# AC_Measure.net
KiCad netlist of a schematic drawn in Altium Designer
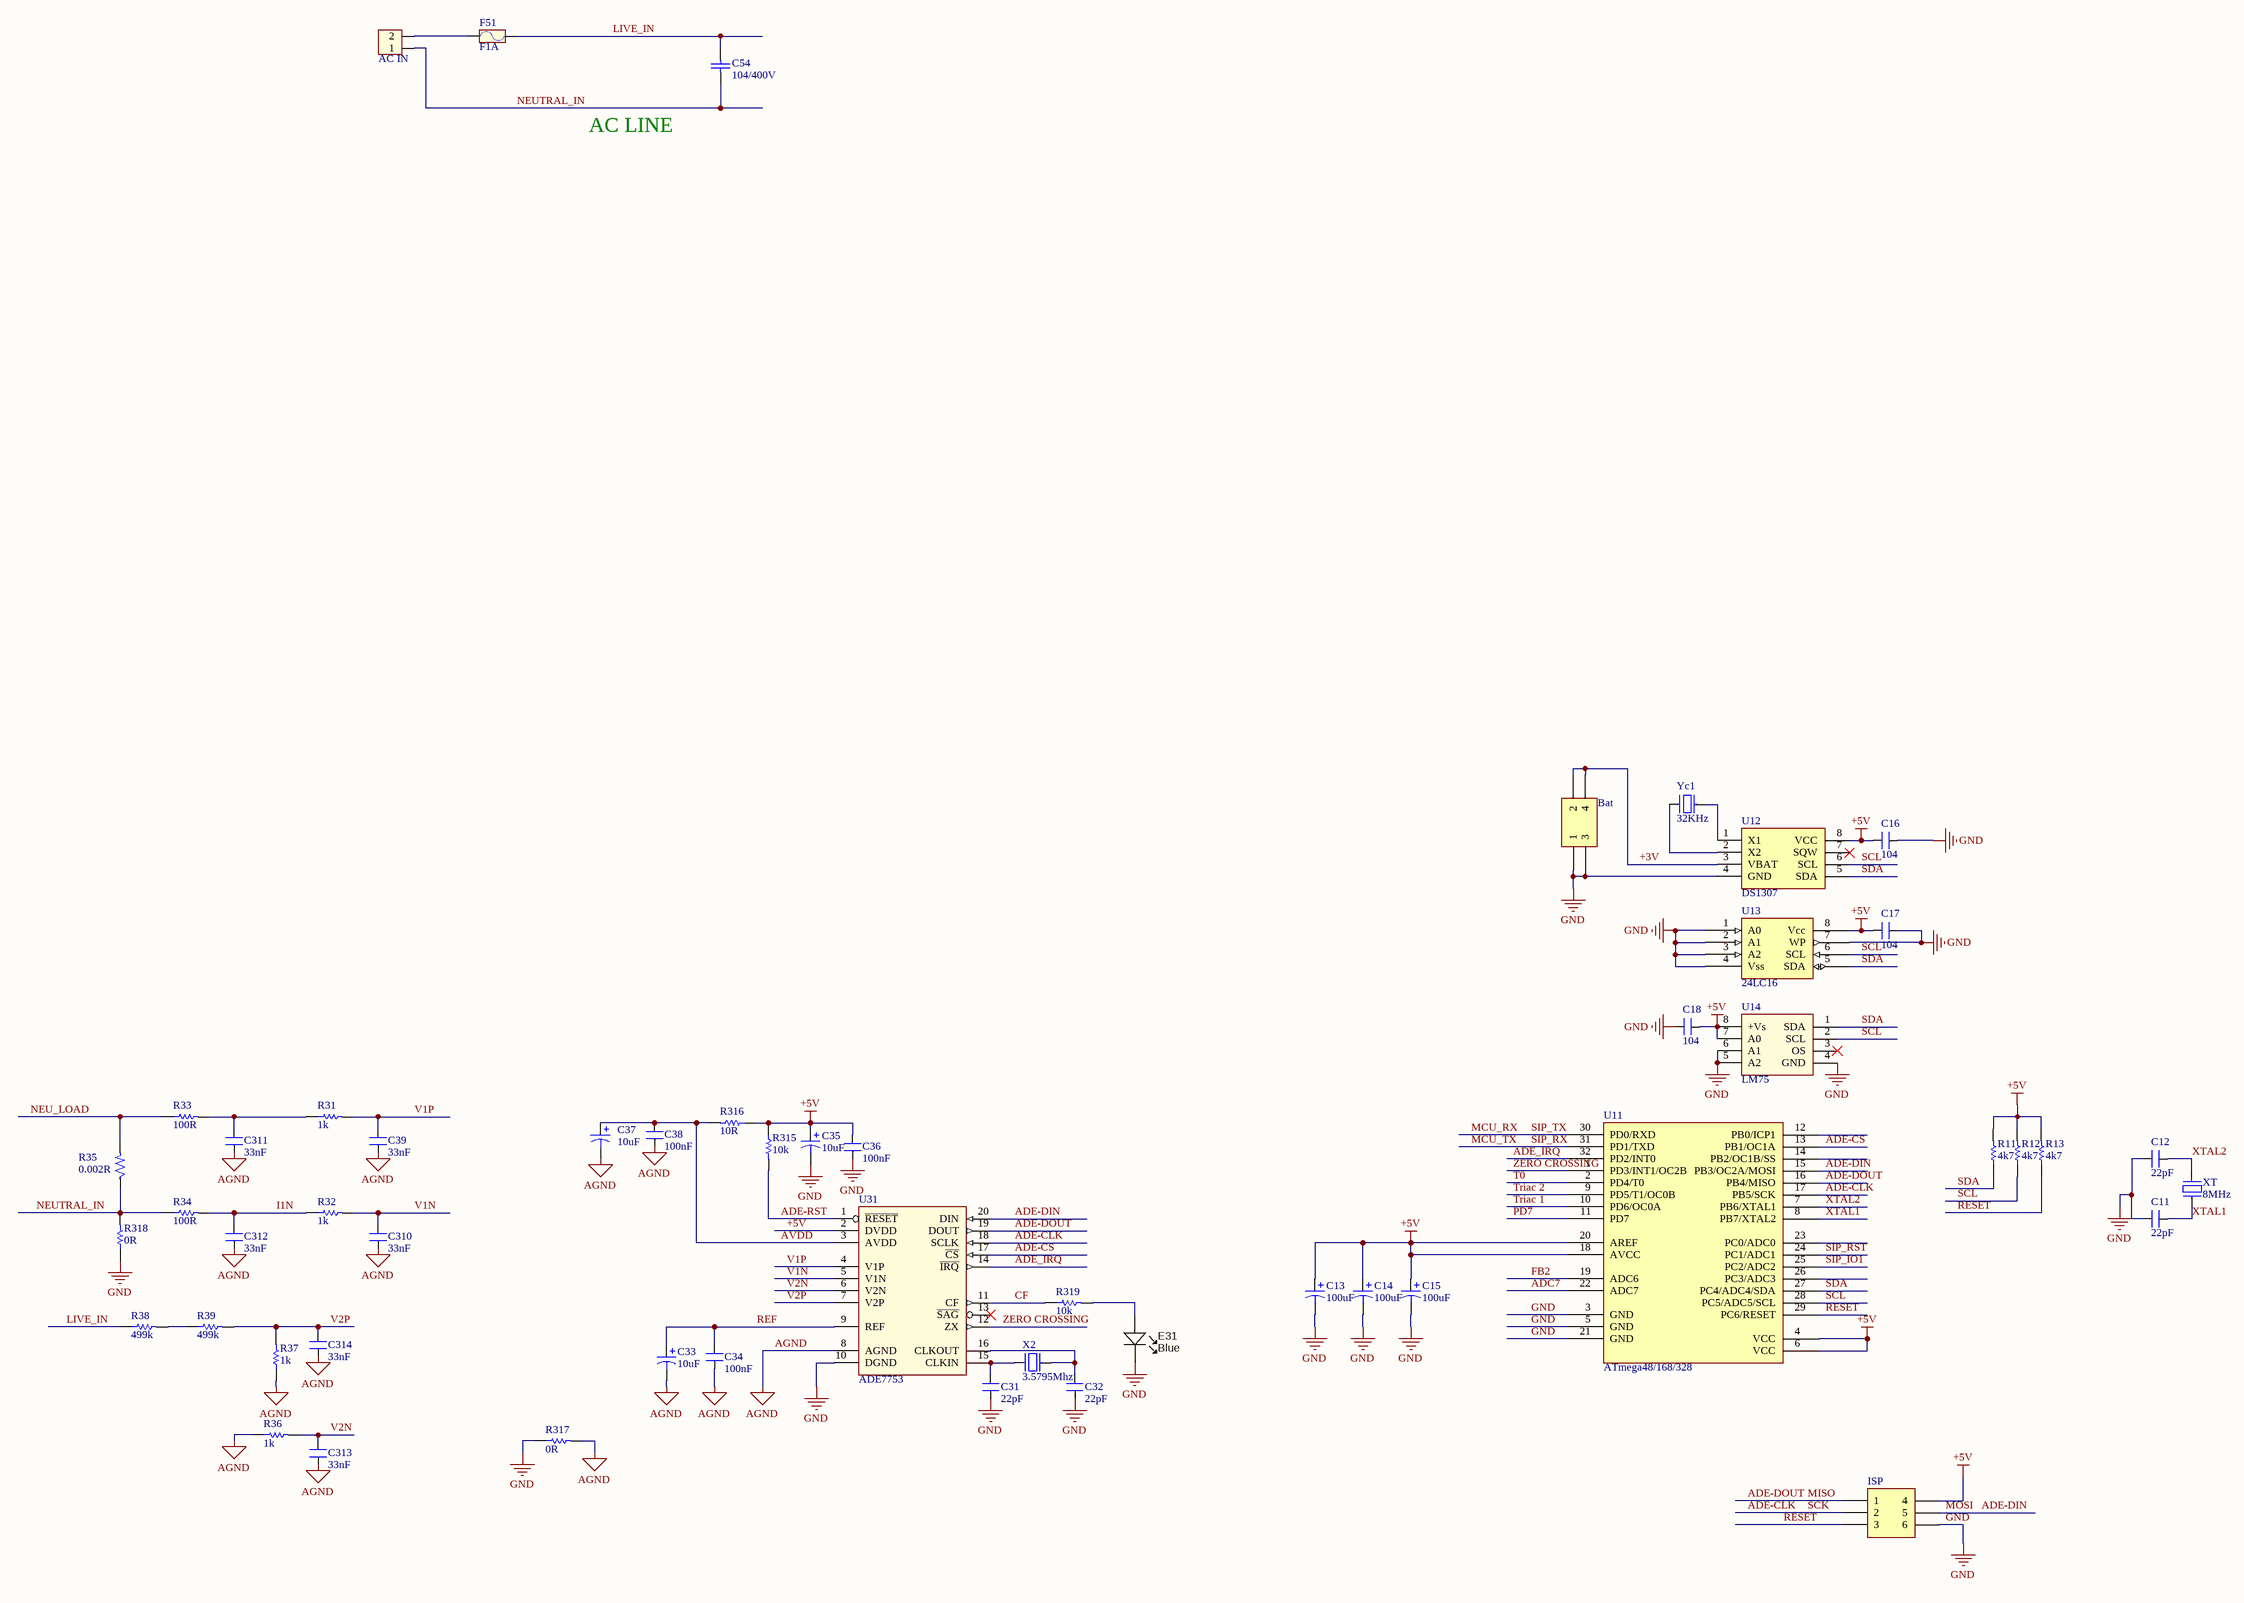
[diagram p0: AC_Measure.SchDoc]

(export (version "E")
  (design (tool "Eeschema 10.0.6"))
  (components
    (comp (ref "AC IN")
      (value "JP2")
      (footprint "CON2")
      (description "Connector 2")
      (libsource (lib "syhaunguyen") (part "Con2"))
    )
    (comp (ref "Bat")
      (value "Header 2X2")
      (footprint "HDR2X2")
      (description "Header, 2-Pin, Dual row")
      (fields (field (name "PUBLISHER") "Altium Limited"))
      (libsource (lib "Miscellaneous Connectors") (part "Header 2X2"))
    )
    (comp (ref "C11")
      (value "22pF")
      (footprint "CAPC1608N")
      (fields (field (name "Comment") "CAP NP"))
      (libsource (lib "Tuan") (part "CAP NP"))
    )
    (comp (ref "C12")
      (value "22pF")
      (footprint "CAPC1608N")
      (fields (field (name "Comment") "CAP NP"))
      (libsource (lib "Tuan") (part "CAP NP"))
    )
    (comp (ref "C13")
      (value "100uF")
      (footprint "CAPC2012N_F")
      (fields (field (name "Comment") "Cap"))
      (libsource (lib "Tuan") (part "Cap"))
    )
    (comp (ref "C14")
      (value "100uF")
      (footprint "CAPC2012N_F")
      (fields (field (name "Comment") "Cap"))
      (libsource (lib "Tuan") (part "Cap"))
    )
    (comp (ref "C15")
      (value "100uF")
      (footprint "CAPC2012N_F")
      (fields (field (name "Comment") "Cap"))
      (libsource (lib "Tuan") (part "Cap"))
    )
    (comp (ref "C16")
      (value "104")
      (footprint "CAPC2012N_F")
      (fields (field (name "Comment") "CAP NP"))
      (libsource (lib "Tuan") (part "CAP NP"))
    )
    (comp (ref "C17")
      (value "104")
      (footprint "CAPC2012N_F")
      (fields (field (name "Comment") "CAP NP"))
      (libsource (lib "Tuan") (part "CAP NP"))
    )
    (comp (ref "C18")
      (value "104")
      (footprint "CAPC2012N_F")
      (fields (field (name "Comment") "CAP NP"))
      (libsource (lib "Tuan") (part "CAP NP"))
    )
    (comp (ref "C31")
      (value "22pF")
      (footprint "CAPC1608N")
      (fields (field (name "Comment") "CAP NP"))
      (libsource (lib "ELS-PLC-2.0") (part "CAP NP"))
    )
    (comp (ref "C32")
      (value "22pF")
      (footprint "CAPC1608N")
      (fields (field (name "Comment") "CAP NP"))
      (libsource (lib "ELS-PLC-2.0") (part "CAP NP"))
    )
    (comp (ref "C33")
      (value "10uF")
      (footprint "CAPC2012N_F")
      (fields (field (name "Comment") "Cap"))
      (libsource (lib "Tuan") (part "Cap"))
    )
    (comp (ref "C34")
      (value "100nF")
      (footprint "CAPC1608N")
      (fields (field (name "Comment") "CAP NP"))
      (libsource (lib "ELS-PLC-2.0") (part "CAP NP"))
    )
    (comp (ref "C35")
      (value "10uF")
      (footprint "CAPC2012N_F")
      (fields (field (name "Comment") "Cap"))
      (libsource (lib "Tuan") (part "Cap"))
    )
    (comp (ref "C36")
      (value "100nF")
      (footprint "CAPC1608N")
      (fields (field (name "Comment") "CAP NP"))
      (libsource (lib "ELS-PLC-2.0") (part "CAP NP"))
    )
    (comp (ref "C37")
      (value "10uF")
      (footprint "CAPC2012N_F")
      (fields (field (name "Comment") "Cap"))
      (libsource (lib "Tuan") (part "Cap"))
    )
    (comp (ref "C38")
      (value "100nF")
      (footprint "CAPC1608N")
      (fields (field (name "Comment") "CAP NP"))
      (libsource (lib "ELS-PLC-2.0") (part "CAP NP"))
    )
    (comp (ref "C39")
      (value "33nF")
      (footprint "CAPC1608N")
      (fields (field (name "Comment") "CAP NP"))
      (libsource (lib "ELS-PLC-2.0") (part "CAP NP"))
    )
    (comp (ref "C54")
      (value "104/400V")
      (footprint "CN3")
      (description "Capacitor")
      (fields (field (name "PUBLISHER") "Altium Limited"))
      (libsource (lib "Miscellaneous Devices") (part "Cap"))
    )
    (comp (ref "C310")
      (value "33nF")
      (footprint "CAPC1608N")
      (fields (field (name "Comment") "CAP NP"))
      (libsource (lib "ELS-PLC-2.0") (part "CAP NP"))
    )
    (comp (ref "C311")
      (value "33nF")
      (footprint "CAPC1608N")
      (fields (field (name "Comment") "CAP NP"))
      (libsource (lib "ELS-PLC-2.0") (part "CAP NP"))
    )
    (comp (ref "C312")
      (value "33nF")
      (footprint "CAPC1608N")
      (fields (field (name "Comment") "CAP NP"))
      (libsource (lib "ELS-PLC-2.0") (part "CAP NP"))
    )
    (comp (ref "C313")
      (value "33nF")
      (footprint "CAPC1608N")
      (fields (field (name "Comment") "CAP NP"))
      (libsource (lib "ELS-PLC-2.0") (part "CAP NP"))
    )
    (comp (ref "C314")
      (value "33nF")
      (footprint "CAPC1608N")
      (fields (field (name "Comment") "CAP NP"))
      (libsource (lib "ELS-PLC-2.0") (part "CAP NP"))
    )
    (comp (ref "E31")
      (value "Blue")
      (footprint "LED-0805-K")
      (description "LED 0805 SMD Blue 100mcd 470nm")
      (fields (field (name "COLOR") "Blue"))
      (libsource (lib "PBL - Light Sources") (part "LED_SMD_Blue_0805_100mcd"))
    )
    (comp (ref "F51")
      (value "F1A")
      (footprint "FUSE2")
      (description "Fuse")
      (fields (field (name "DESIGNED BY") "VanDungEvn"))
      (libsource (lib "syhaunguyen") (part "Fuse"))
    )
    (comp (ref "ISP")
      (value "Header 3X2A")
      (footprint "HDR2X3_CEN")
      (description "Header, 3-Pin, Dual row")
      (fields (field (name "PUBLISHER") "Altium Limited"))
      (libsource (lib "Miscellaneous Connectors") (part "Header 3X2A"))
    )
    (comp (ref "R11")
      (value "4k7")
      (footprint "RESC1608N_ZERO")
      (fields (field (name "Comment") "Res"))
      (libsource (lib "Tuan") (part "Res"))
    )
    (comp (ref "R12")
      (value "4k7")
      (footprint "RESC1608N_ZERO")
      (fields (field (name "Comment") "Res"))
      (libsource (lib "Tuan") (part "Res"))
    )
    (comp (ref "R13")
      (value "4k7")
      (footprint "RESC1608N_ZERO")
      (fields (field (name "Comment") "Res"))
      (libsource (lib "Tuan") (part "Res"))
    )
    (comp (ref "R31")
      (value "1k")
      (footprint "RESC1608N_ZERO")
      (fields (field (name "Comment") "Res"))
      (libsource (lib "Tuan") (part "Res"))
    )
    (comp (ref "R32")
      (value "1k")
      (footprint "RESC1608N_ZERO")
      (fields (field (name "Comment") "Res"))
      (libsource (lib "Tuan") (part "Res"))
    )
    (comp (ref "R33")
      (value "100R")
      (footprint "RESC1608N_ZERO")
      (fields (field (name "Comment") "Res"))
      (libsource (lib "Tuan") (part "Res"))
    )
    (comp (ref "R34")
      (value "100R")
      (footprint "RESC1608N_ZERO")
      (fields (field (name "Comment") "Res"))
      (libsource (lib "Tuan") (part "Res"))
    )
    (comp (ref "R35")
      (value "0.002R")
      (footprint "RESC6332N")
      (description "Resistor 1/4W")
      (libsource (lib "syhaunguyen") (part "R"))
    )
    (comp (ref "R36")
      (value "1k")
      (footprint "RESC1608N_ZERO")
      (fields (field (name "Comment") "Res"))
      (libsource (lib "Tuan") (part "Res"))
    )
    (comp (ref "R37")
      (value "1k")
      (footprint "RESC1608N_ZERO")
      (fields (field (name "Comment") "Res"))
      (libsource (lib "Tuan") (part "Res"))
    )
    (comp (ref "R38")
      (value "499k")
      (footprint "RESC2012N_F")
      (fields (field (name "Comment") "Res"))
      (libsource (lib "Tuan") (part "Res"))
    )
    (comp (ref "R39")
      (value "499k")
      (footprint "RESC2012N_F")
      (fields (field (name "Comment") "Res"))
      (libsource (lib "Tuan") (part "Res"))
    )
    (comp (ref "R315")
      (value "10k")
      (footprint "RESC1608N_ZERO")
      (fields (field (name "Comment") "Res"))
      (libsource (lib "Tuan") (part "Res"))
    )
    (comp (ref "R316")
      (value "10R")
      (footprint "RESC2012N_F")
      (fields (field (name "Comment") "Res"))
      (libsource (lib "Tuan") (part "Res"))
    )
    (comp (ref "R317")
      (value "0R")
      (footprint "RESC2012N_F")
      (fields (field (name "Comment") "Res"))
      (libsource (lib "Tuan") (part "Res"))
    )
    (comp (ref "R318")
      (value "0R")
      (footprint "RESC2012N_F")
      (fields (field (name "Comment") "Res"))
      (libsource (lib "Tuan") (part "Res"))
    )
    (comp (ref "R319")
      (value "10k")
      (footprint "RESC1608N_ZERO")
      (fields (field (name "Comment") "Res"))
      (libsource (lib "Tuan") (part "Res"))
    )
    (comp (ref "U11")
      (value "ATmega48/168/328")
      (footprint "32A_N")
      (libsource (lib "Tuan") (part "ATmega48/168/328"))
    )
    (comp (ref "U12")
      (value "DS1307")
      (footprint "SOIC-8")
      (description "Real Timer Serial")
      (libsource (lib "MLab Miscellaneous Devices") (part "DS1307"))
    )
    (comp (ref "U13")
      (value "24LC16")
      (footprint "SOIC-8")
      (libsource (lib "PhamTu_IntLib") (part "24LC04B"))
    )
    (comp (ref "U14") (value "LM75") (footprint "SOIC-8") (libsource (lib "heromap") (part "LM75")))
    (comp (ref "U31")
      (value "ADE7753")
      (footprint "TSSOP-20")
      (description "Single-Phase Multifunction Metering IC with di/dt Sensor Interface")
      (libsource (lib "heromap") (part "ADE7753"))
    )
    (comp (ref "X2")
      (value "3.5795Mhz")
      (footprint "heromap:XT2")
      (description "Crystal For all Crystal 2pin.")
      (libsource (lib "heromap") (part "XT2"))
    )
    (comp (ref "XT") (value "8MHz") (footprint "XT2") (libsource (lib "Tuan") (part "Crystal")))
    (comp (ref "Yc1")
      (value "32KHz")
      (footprint "XTminiv2")
      (description "Crystal For all Crystal 2pin.")
      (libsource (lib "syhaunguyen") (part "XT2"))
    )
  )
  (nets
    (net (code "1") (name "+5V") (class "Default")
      (node (ref "C13") (pin "1") (pinfunction "1_1") (pintype "passive"))
      (node (ref "C14") (pin "1") (pinfunction "1_1") (pintype "passive"))
      (node (ref "C15") (pin "1") (pinfunction "1_1") (pintype "passive"))
      (node (ref "C16") (pin "1") (pinfunction "1_1") (pintype "passive"))
      (node (ref "C17") (pin "1") (pinfunction "1_1") (pintype "passive"))
      (node (ref "C18") (pin "2") (pinfunction "2_2") (pintype "passive"))
      (node (ref "C35") (pin "1") (pinfunction "1_1") (pintype "passive"))
      (node (ref "C36") (pin "2") (pinfunction "2_2") (pintype "passive"))
      (node (ref "ISP") (pin "4") (pinfunction "4_4") (pintype "passive"))
      (node (ref "R11") (pin "2") (pinfunction "2_2") (pintype "passive"))
      (node (ref "R12") (pin "2") (pinfunction "2_2") (pintype "passive"))
      (node (ref "R13") (pin "2") (pinfunction "2_2") (pintype "passive"))
      (node (ref "R315") (pin "1") (pinfunction "1_1") (pintype "passive"))
      (node (ref "R316") (pin "1") (pinfunction "1_1") (pintype "passive"))
      (node (ref "U11") (pin "18") (pinfunction "AVCC_18") (pintype "passive"))
      (node (ref "U11") (pin "20") (pinfunction "AREF_20") (pintype "passive"))
      (node (ref "U11") (pin "4") (pinfunction "VCC_4") (pintype "passive"))
      (node (ref "U11") (pin "6") (pinfunction "VCC_6") (pintype "passive"))
      (node (ref "U12") (pin "8") (pinfunction "VCC_8") (pintype "passive"))
      (node (ref "U13") (pin "8") (pinfunction "Vcc_8") (pintype "power_in"))
      (node (ref "U14") (pin "7") (pinfunction "A0_7") (pintype "passive"))
      (node (ref "U14") (pin "8") (pinfunction "+Vs_8") (pintype "power_in"))
      (node (ref "U31") (pin "2") (pinfunction "DVDD_2") (pintype "passive"))
    )
    (net (code "2") (name "/+3V") (class "Default")
      (node (ref "Bat") (pin "2") (pinfunction "2_2") (pintype "passive"))
      (node (ref "Bat") (pin "4") (pinfunction "4_4") (pintype "passive"))
      (node (ref "U12") (pin "3") (pinfunction "VBAT_3") (pintype "passive"))
    )
    (net (code "3") (name "/ADC7") (class "Default")
      (node (ref "U11") (pin "22") (pinfunction "ADC7_22") (pintype "passive"))
    )
    (net (code "4") (name "/ADE-CLK") (class "Default")
      (node (ref "ISP") (pin "2") (pinfunction "2_2") (pintype "passive"))
      (node (ref "U11") (pin "17") (pinfunction "PB5/SCK_17") (pintype "passive"))
      (node (ref "U31") (pin "18") (pinfunction "SCLK_18") (pintype "input"))
    )
    (net (code "5") (name "/ADE-CS") (class "Default")
      (node (ref "U11") (pin "13") (pinfunction "PB1/OC1A_13") (pintype "passive"))
      (node (ref "U31") (pin "17") (pinfunction "~{CS}_17") (pintype "input"))
    )
    (net (code "6") (name "/ADE-DIN") (class "Default")
      (node (ref "ISP") (pin "5") (pinfunction "5_5") (pintype "passive"))
      (node (ref "U11") (pin "15") (pinfunction "PB3/OC2A/MOSI_15") (pintype "passive"))
      (node (ref "U31") (pin "20") (pinfunction "DIN_20") (pintype "input"))
    )
    (net (code "7") (name "/ADE-DOUT") (class "Default")
      (node (ref "ISP") (pin "1") (pinfunction "1_1") (pintype "passive"))
      (node (ref "U11") (pin "16") (pinfunction "PB4/MISO_16") (pintype "passive"))
      (node (ref "U31") (pin "19") (pinfunction "DOUT_19") (pintype "output"))
    )
    (net (code "8") (name "/ADE-RST") (class "Default")
      (node (ref "R315") (pin "2") (pinfunction "2_2") (pintype "passive"))
      (node (ref "U31") (pin "1") (pinfunction "~{RESET}_1") (pintype "passive"))
    )
    (net (code "9") (name "/ADE_IRQ") (class "Default")
      (node (ref "U11") (pin "32") (pinfunction "PD2/INT0_32") (pintype "passive"))
      (node (ref "U31") (pin "14") (pinfunction "~{IRQ}_14") (pintype "output"))
    )
    (net (code "10") (name "/AVDD") (class "Default")
      (node (ref "C37") (pin "1") (pinfunction "1_1") (pintype "passive"))
      (node (ref "C38") (pin "2") (pinfunction "2_2") (pintype "passive"))
      (node (ref "R316") (pin "2") (pinfunction "2_2") (pintype "passive"))
      (node (ref "U31") (pin "3") (pinfunction "AVDD_3") (pintype "passive"))
    )
    (net (code "11") (name "/CF") (class "Default")
      (node (ref "R319") (pin "1") (pinfunction "1_1") (pintype "passive"))
      (node (ref "U31") (pin "11") (pinfunction "CF_11") (pintype "output"))
    )
    (net (code "12") (name "/FB2") (class "Default")
      (node (ref "U11") (pin "19") (pinfunction "ADC6_19") (pintype "passive"))
    )
    (net (code "13") (name "/I1N") (class "Default")
      (node (ref "C312") (pin "2") (pinfunction "2_2") (pintype "passive"))
      (node (ref "R32") (pin "1") (pinfunction "1_1") (pintype "passive"))
      (node (ref "R34") (pin "2") (pinfunction "2_2") (pintype "passive"))
    )
    (net (code "14") (name "/LIVE_IN") (class "Default")
      (node (ref "C54") (pin "2") (pinfunction "2_2") (pintype "passive"))
      (node (ref "F51") (pin "2") (pinfunction "2_2") (pintype "passive"))
      (node (ref "R38") (pin "1") (pinfunction "1_1") (pintype "passive"))
    )
    (net (code "15") (name "/MCU_RX") (class "Default")
      (node (ref "U11") (pin "30") (pinfunction "PD0/RXD_30") (pintype "passive"))
    )
    (net (code "16") (name "/MCU_TX") (class "Default")
      (node (ref "U11") (pin "31") (pinfunction "PD1/TXD_31") (pintype "passive"))
    )
    (net (code "17") (name "/NEUTRAL_IN") (class "Default")
      (node (ref "AC IN") (pin "1") (pinfunction "1_1") (pintype "passive"))
      (node (ref "C54") (pin "1") (pinfunction "1_1") (pintype "passive"))
      (node (ref "R318") (pin "2") (pinfunction "2_2") (pintype "passive"))
      (node (ref "R34") (pin "1") (pinfunction "1_1") (pintype "passive"))
      (node (ref "R35") (pin "1") (pinfunction "1_1") (pintype "passive"))
    )
    (net (code "18") (name "/NEU_LOAD") (class "Default")
      (node (ref "R33") (pin "1") (pinfunction "1_1") (pintype "passive"))
      (node (ref "R35") (pin "2") (pinfunction "2_2") (pintype "passive"))
    )
    (net (code "19") (name "/PD7") (class "Default")
      (node (ref "U11") (pin "11") (pinfunction "PD7_11") (pintype "passive"))
    )
    (net (code "20") (name "/REF") (class "Default")
      (node (ref "C33") (pin "1") (pinfunction "1_1") (pintype "passive"))
      (node (ref "C34") (pin "2") (pinfunction "2_2") (pintype "passive"))
      (node (ref "U31") (pin "9") (pinfunction "REF_9") (pintype "passive"))
    )
    (net (code "21") (name "/RESET") (class "Default")
      (node (ref "ISP") (pin "3") (pinfunction "3_3") (pintype "passive"))
      (node (ref "R13") (pin "1") (pinfunction "1_1") (pintype "passive"))
      (node (ref "U11") (pin "29") (pinfunction "PC6/RESET_29") (pintype "passive"))
    )
    (net (code "22") (name "/SCL") (class "Default")
      (node (ref "R12") (pin "1") (pinfunction "1_1") (pintype "passive"))
      (node (ref "U11") (pin "28") (pinfunction "PC5/ADC5/SCL_28") (pintype "passive"))
      (node (ref "U12") (pin "6") (pinfunction "SCL_6") (pintype "passive"))
      (node (ref "U13") (pin "6") (pinfunction "SCL_6") (pintype "input"))
      (node (ref "U14") (pin "2") (pinfunction "SCL_2") (pintype "passive"))
    )
    (net (code "23") (name "/SDA") (class "Default")
      (node (ref "R11") (pin "1") (pinfunction "1_1") (pintype "passive"))
      (node (ref "U11") (pin "27") (pinfunction "PC4/ADC4/SDA_27") (pintype "passive"))
      (node (ref "U12") (pin "5") (pinfunction "SDA_5") (pintype "passive"))
      (node (ref "U13") (pin "5") (pinfunction "SDA_5") (pintype "bidirectional"))
      (node (ref "U14") (pin "1") (pinfunction "SDA_1") (pintype "passive"))
    )
    (net (code "24") (name "/SIP_IO1") (class "Default")
      (node (ref "U11") (pin "25") (pinfunction "PC2/ADC2_25") (pintype "passive"))
    )
    (net (code "25") (name "/SIP_RST") (class "Default")
      (node (ref "U11") (pin "24") (pinfunction "PC1/ADC1_24") (pintype "passive"))
    )
    (net (code "26") (name "/T0") (class "Default")
      (node (ref "U11") (pin "2") (pinfunction "PD4/T0_2") (pintype "passive"))
    )
    (net (code "27") (name "/Triac 1") (class "Default")
      (node (ref "U11") (pin "10") (pinfunction "PD6/OC0A_10") (pintype "passive"))
    )
    (net (code "28") (name "/Triac 2") (class "Default")
      (node (ref "U11") (pin "9") (pinfunction "PD5/T1/OC0B_9") (pintype "passive"))
    )
    (net (code "29") (name "/V1N") (class "Default")
      (node (ref "C310") (pin "2") (pinfunction "2_2") (pintype "passive"))
      (node (ref "R32") (pin "2") (pinfunction "2_2") (pintype "passive"))
      (node (ref "U31") (pin "5") (pinfunction "V1N_5") (pintype "passive"))
    )
    (net (code "30") (name "/V1P") (class "Default")
      (node (ref "C39") (pin "2") (pinfunction "2_2") (pintype "passive"))
      (node (ref "R31") (pin "2") (pinfunction "2_2") (pintype "passive"))
      (node (ref "U31") (pin "4") (pinfunction "V1P_4") (pintype "passive"))
    )
    (net (code "31") (name "/V2N") (class "Default")
      (node (ref "C313") (pin "2") (pinfunction "2_2") (pintype "passive"))
      (node (ref "R36") (pin "2") (pinfunction "2_2") (pintype "passive"))
      (node (ref "U31") (pin "6") (pinfunction "V2N_6") (pintype "passive"))
    )
    (net (code "32") (name "/V2P") (class "Default")
      (node (ref "C314") (pin "2") (pinfunction "2_2") (pintype "passive"))
      (node (ref "R37") (pin "2") (pinfunction "2_2") (pintype "passive"))
      (node (ref "R39") (pin "2") (pinfunction "2_2") (pintype "passive"))
      (node (ref "U31") (pin "7") (pinfunction "V2P_7") (pintype "passive"))
    )
    (net (code "33") (name "/XTAL1") (class "Default")
      (node (ref "C11") (pin "1") (pinfunction "1_1") (pintype "passive"))
      (node (ref "U11") (pin "8") (pinfunction "PB7/XTAL2_8") (pintype "passive"))
      (node (ref "XT") (pin "1") (pinfunction "1_1") (pintype "passive"))
    )
    (net (code "34") (name "/XTAL2") (class "Default")
      (node (ref "C12") (pin "1") (pinfunction "1_1") (pintype "passive"))
      (node (ref "U11") (pin "7") (pinfunction "PB6/XTAL1_7") (pintype "passive"))
      (node (ref "XT") (pin "2") (pinfunction "2_2") (pintype "passive"))
    )
    (net (code "35") (name "/ZERO CROSSING") (class "Default")
      (node (ref "U11") (pin "1") (pinfunction "PD3/INT1/OC2B_1") (pintype "passive"))
      (node (ref "U31") (pin "12") (pinfunction "ZX_12") (pintype "output"))
    )
    (net (code "36") (name "AGND") (class "Default")
      (node (ref "C310") (pin "1") (pinfunction "1_1") (pintype "passive"))
      (node (ref "C311") (pin "1") (pinfunction "1_1") (pintype "passive"))
      (node (ref "C312") (pin "1") (pinfunction "1_1") (pintype "passive"))
      (node (ref "C313") (pin "1") (pinfunction "1_1") (pintype "passive"))
      (node (ref "C314") (pin "1") (pinfunction "1_1") (pintype "passive"))
      (node (ref "C33") (pin "2") (pinfunction "2_2") (pintype "passive"))
      (node (ref "C34") (pin "1") (pinfunction "1_1") (pintype "passive"))
      (node (ref "C37") (pin "2") (pinfunction "2_2") (pintype "passive"))
      (node (ref "C38") (pin "1") (pinfunction "1_1") (pintype "passive"))
      (node (ref "C39") (pin "1") (pinfunction "1_1") (pintype "passive"))
      (node (ref "R317") (pin "2") (pinfunction "2_2") (pintype "passive"))
      (node (ref "R36") (pin "1") (pinfunction "1_1") (pintype "passive"))
      (node (ref "R37") (pin "1") (pinfunction "1_1") (pintype "passive"))
      (node (ref "U31") (pin "8") (pinfunction "AGND_8") (pintype "passive"))
    )
    (net (code "37") (name "GND") (class "Default")
      (node (ref "Bat") (pin "1") (pinfunction "1_1") (pintype "passive"))
      (node (ref "Bat") (pin "3") (pinfunction "3_3") (pintype "passive"))
      (node (ref "C11") (pin "2") (pinfunction "2_2") (pintype "passive"))
      (node (ref "C12") (pin "2") (pinfunction "2_2") (pintype "passive"))
      (node (ref "C13") (pin "2") (pinfunction "2_2") (pintype "passive"))
      (node (ref "C14") (pin "2") (pinfunction "2_2") (pintype "passive"))
      (node (ref "C15") (pin "2") (pinfunction "2_2") (pintype "passive"))
      (node (ref "C16") (pin "2") (pinfunction "2_2") (pintype "passive"))
      (node (ref "C17") (pin "2") (pinfunction "2_2") (pintype "passive"))
      (node (ref "C18") (pin "1") (pinfunction "1_1") (pintype "passive"))
      (node (ref "C31") (pin "1") (pinfunction "1_1") (pintype "passive"))
      (node (ref "C32") (pin "1") (pinfunction "1_1") (pintype "passive"))
      (node (ref "C35") (pin "2") (pinfunction "2_2") (pintype "passive"))
      (node (ref "C36") (pin "1") (pinfunction "1_1") (pintype "passive"))
      (node (ref "E31") (pin "K") (pinfunction "K_K") (pintype "passive"))
      (node (ref "ISP") (pin "6") (pinfunction "6_6") (pintype "passive"))
      (node (ref "R317") (pin "1") (pinfunction "1_1") (pintype "passive"))
      (node (ref "R318") (pin "1") (pinfunction "1_1") (pintype "passive"))
      (node (ref "U11") (pin "21") (pinfunction "GND_21") (pintype "power_in"))
      (node (ref "U11") (pin "3") (pinfunction "GND_3") (pintype "power_in"))
      (node (ref "U11") (pin "5") (pinfunction "GND_5") (pintype "power_in"))
      (node (ref "U12") (pin "4") (pinfunction "GND_4") (pintype "passive"))
      (node (ref "U13") (pin "1") (pinfunction "A0_1") (pintype "input"))
      (node (ref "U13") (pin "2") (pinfunction "A1_2") (pintype "input"))
      (node (ref "U13") (pin "3") (pinfunction "A2_3") (pintype "input"))
      (node (ref "U13") (pin "4") (pinfunction "Vss_4") (pintype "power_in"))
      (node (ref "U13") (pin "7") (pinfunction "WP_7") (pintype "output"))
      (node (ref "U14") (pin "4") (pinfunction "GND_4") (pintype "power_in"))
      (node (ref "U14") (pin "5") (pinfunction "A2_5") (pintype "passive"))
      (node (ref "U14") (pin "6") (pinfunction "A1_6") (pintype "passive"))
      (node (ref "U31") (pin "10") (pinfunction "DGND_10") (pintype "passive"))
    )
    (net (code "38") (name "Net-(AC IN-Pad2)") (class "Default")
      (node (ref "AC IN") (pin "2") (pinfunction "2_2") (pintype "passive"))
      (node (ref "F51") (pin "1") (pinfunction "1_1") (pintype "passive"))
    )
    (net (code "39") (name "Net-(C311-Pad2)") (class "Default")
      (node (ref "C311") (pin "2") (pinfunction "2_2") (pintype "passive"))
      (node (ref "R31") (pin "1") (pinfunction "1_1") (pintype "passive"))
      (node (ref "R33") (pin "2") (pinfunction "2_2") (pintype "passive"))
    )
    (net (code "40") (name "Net-(E31-PadA)") (class "Default")
      (node (ref "E31") (pin "A") (pinfunction "A_A") (pintype "passive"))
      (node (ref "R319") (pin "2") (pinfunction "2_2") (pintype "passive"))
    )
    (net (code "41") (name "Net-(R38-Pad2)") (class "Default")
      (node (ref "R38") (pin "2") (pinfunction "2_2") (pintype "passive"))
      (node (ref "R39") (pin "1") (pinfunction "1_1") (pintype "passive"))
    )
    (net (code "42") (name "Net-(U12-X1)") (class "Default")
      (node (ref "U12") (pin "1") (pinfunction "X1_1") (pintype "passive"))
      (node (ref "Yc1") (pin "1") (pinfunction "1_1") (pintype "passive"))
    )
    (net (code "43") (name "Net-(U12-X2)") (class "Default")
      (node (ref "U12") (pin "2") (pinfunction "X2_2") (pintype "passive"))
      (node (ref "Yc1") (pin "2") (pinfunction "2_2") (pintype "passive"))
    )
    (net (code "44") (name "Net-(U31-CLKIN)") (class "Default")
      (node (ref "C31") (pin "2") (pinfunction "2_2") (pintype "passive"))
      (node (ref "U31") (pin "15") (pinfunction "CLKIN_15") (pintype "passive"))
      (node (ref "X2") (pin "2") (pinfunction "2_2") (pintype "passive"))
    )
    (net (code "45") (name "Net-(U31-CLKOUT)") (class "Default")
      (node (ref "C32") (pin "2") (pinfunction "2_2") (pintype "passive"))
      (node (ref "U31") (pin "16") (pinfunction "CLKOUT_16") (pintype "passive"))
      (node (ref "X2") (pin "1") (pinfunction "1_1") (pintype "passive"))
    )
    (net (code "46") (name "unconnected-(U11-PB0{slash}ICP1-Pad12)") (class "Default")
      (node (ref "U11") (pin "12") (pinfunction "PB0/ICP1_12") (pintype "passive"))
    )
    (net (code "47") (name "unconnected-(U11-PB2{slash}OC1B{slash}SS-Pad14)") (class "Default")
      (node (ref "U11") (pin "14") (pinfunction "PB2/OC1B/SS_14") (pintype "passive"))
    )
    (net (code "48") (name "unconnected-(U11-PC0{slash}ADC0-Pad23)") (class "Default")
      (node (ref "U11") (pin "23") (pinfunction "PC0/ADC0_23") (pintype "passive"))
    )
    (net (code "49") (name "unconnected-(U11-PC3{slash}ADC3-Pad26)") (class "Default")
      (node (ref "U11") (pin "26") (pinfunction "PC3/ADC3_26") (pintype "passive"))
    )
    (net (code "50") (name "unconnected-(U12-SQW-Pad7)") (class "Default")
      (node (ref "U12") (pin "7") (pinfunction "SQW_7") (pintype "passive+no_connect"))
    )
    (net (code "51") (name "unconnected-(U14-OS-Pad3)") (class "Default")
      (node (ref "U14") (pin "3") (pinfunction "OS_3") (pintype "passive+no_connect"))
    )
    (net (code "52") (name "unconnected-(U31-~{SAG}-Pad13)") (class "Default")
      (node (ref "U31") (pin "13") (pinfunction "~{SAG}_13") (pintype "passive+no_connect"))
    )
  )
)
